# BEP3_RPM_BAR_multi.net
KiCad netlist of a schematic drawn in EAGLE
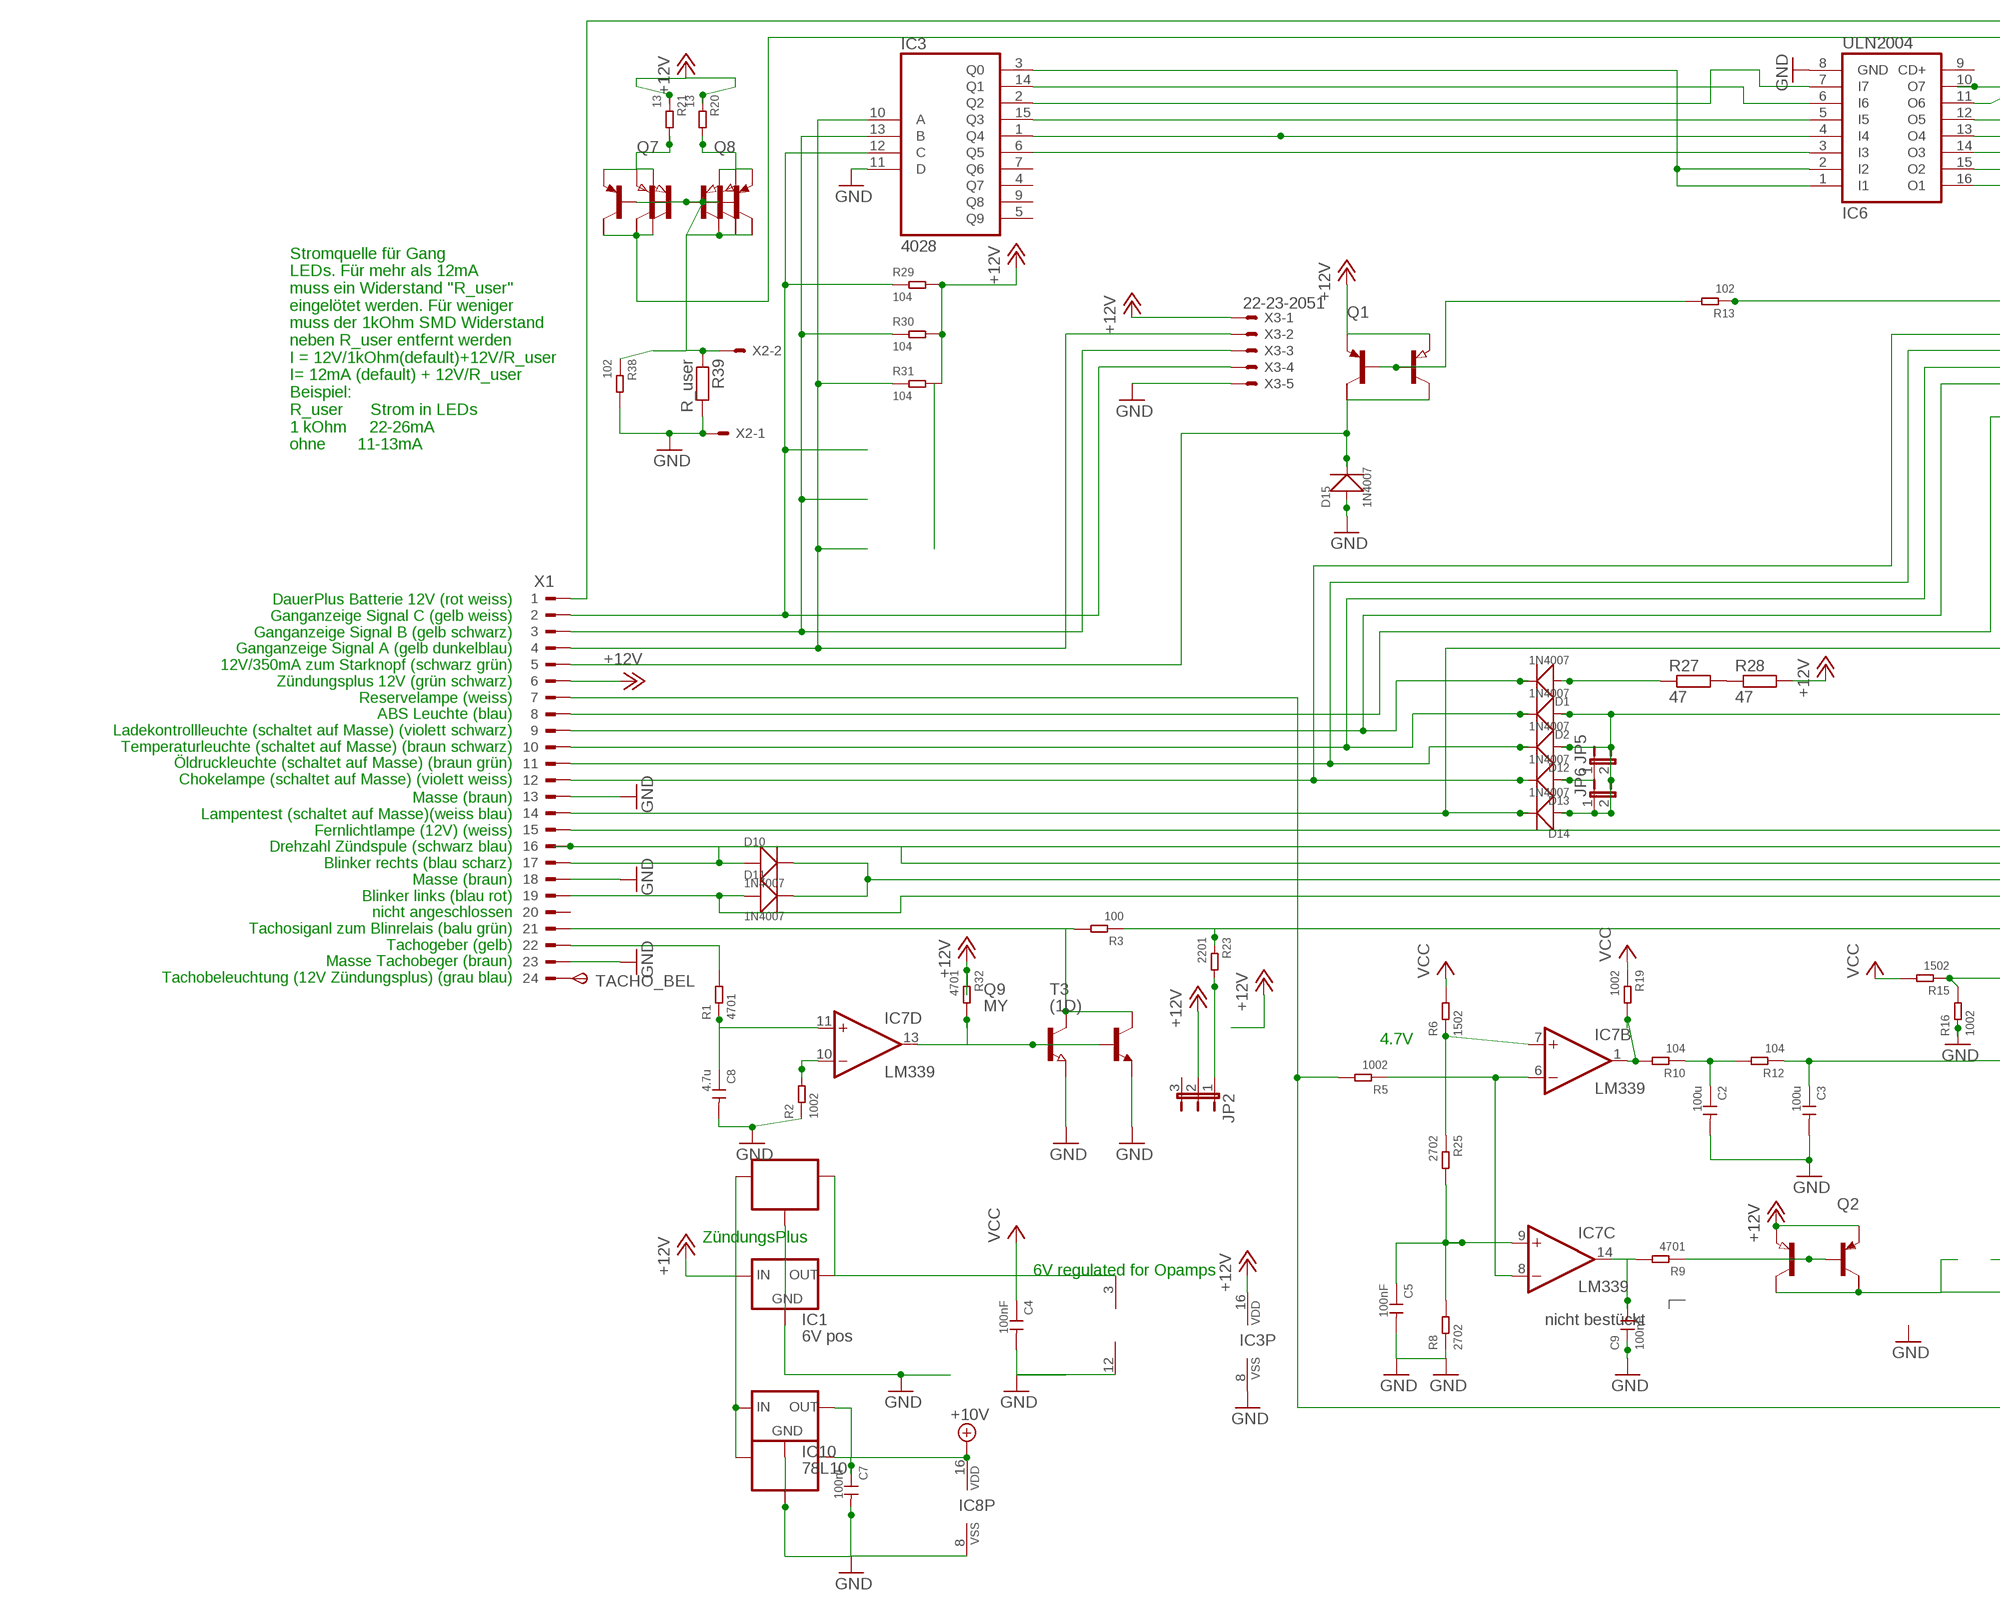
[diagram p0: schematic, sheet 1, part 1 of 2]
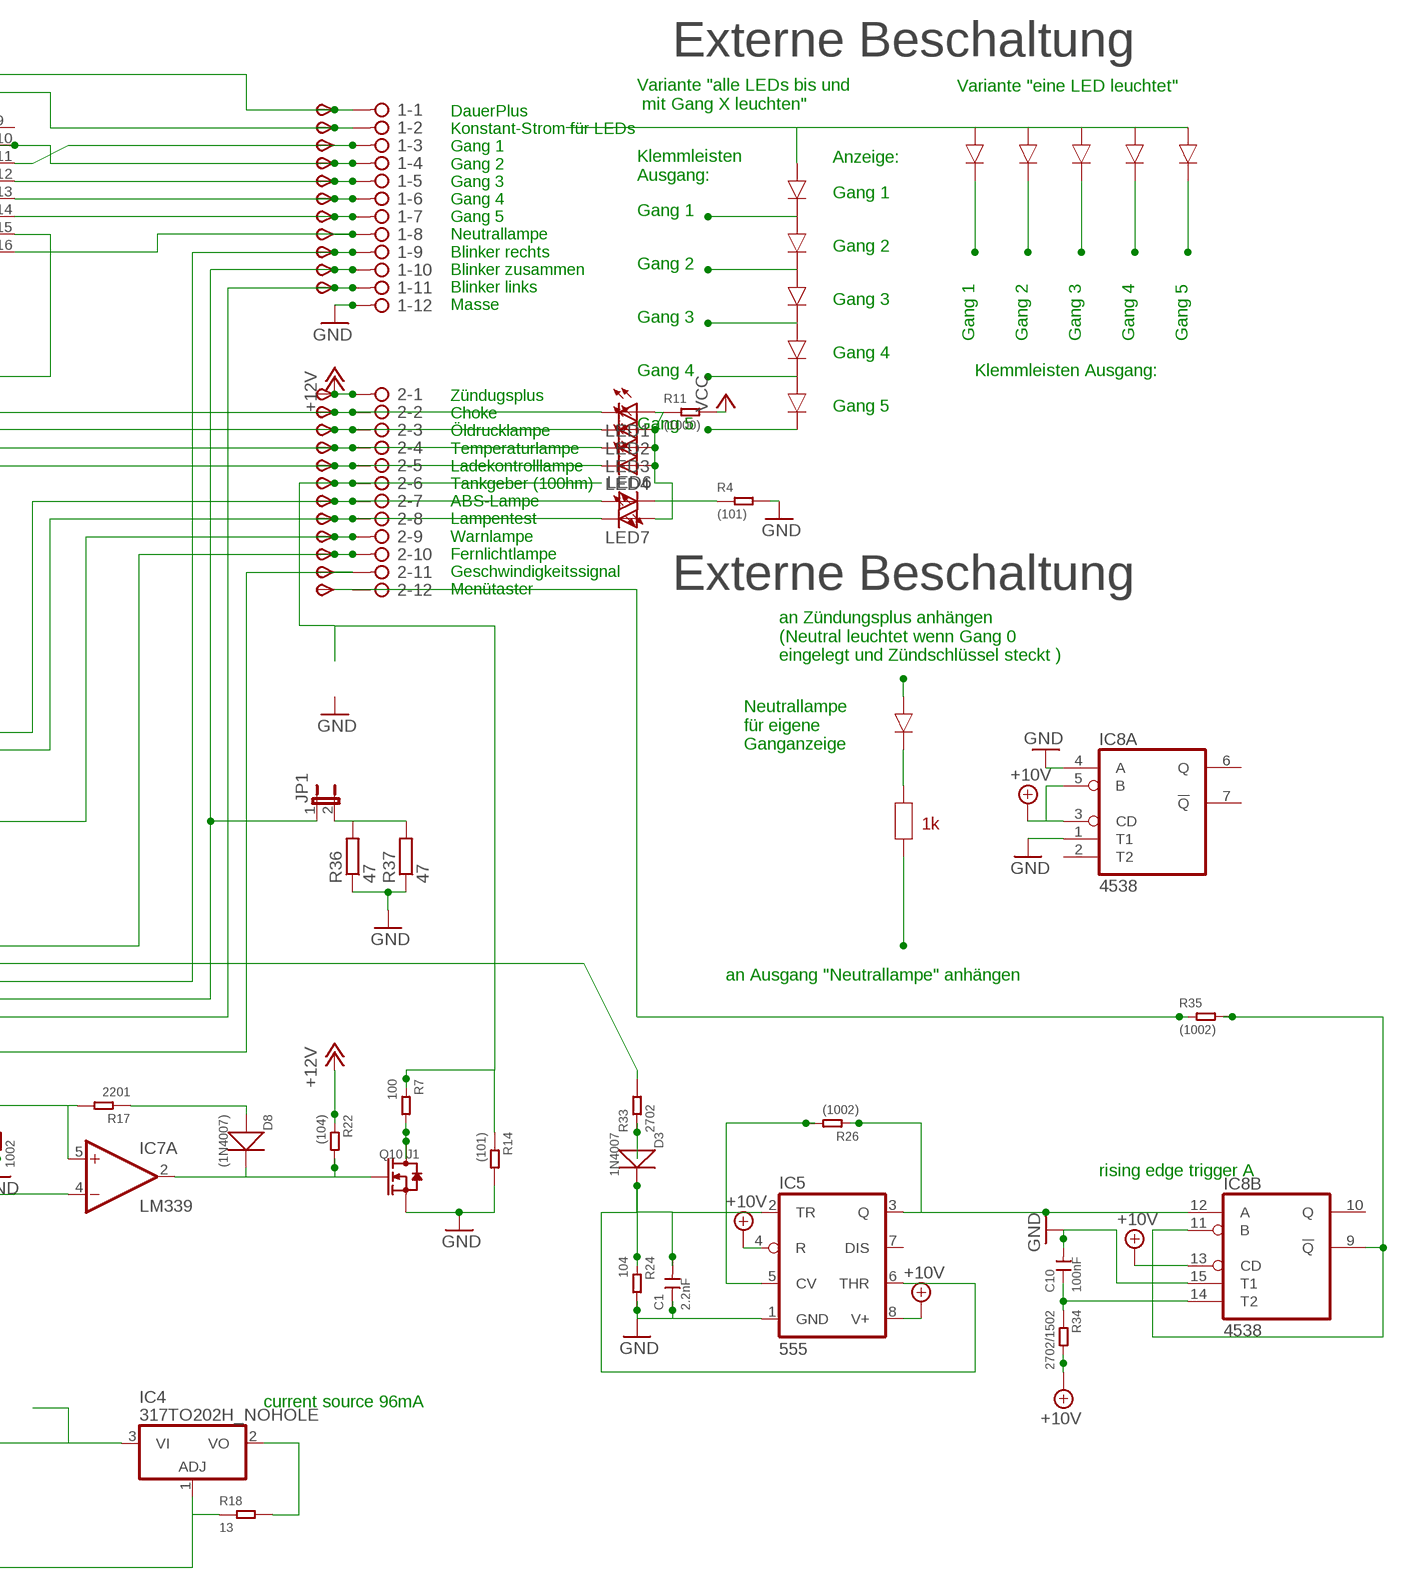
[diagram p1: schematic, sheet 1, part 2 of 2]

(export (version "E")
  (design (tool "Eeschema 10.0.6"))
  (components
    (comp (ref "1")
      (value "2081-1132")
      (footprint "eagle-import:12-PIN")
      (libsource (lib "eagle-import") (part "2081-1132"))
    )
    (comp (ref "2")
      (value "2081-1132")
      (footprint "eagle-import:12-PIN")
      (libsource (lib "eagle-import") (part "2081-1132"))
    )
    (comp (ref "C1")
      (value "2.2nF")
      (footprint "eagle-import:C0805")
      (fields (field (name "MPN") "CC0805KRX7R9BB104"))
      (libsource (lib "eagle-import") (part "CERAMIC-100NF-50V-10%-X7R(0805)"))
    )
    (comp (ref "C2")
      (value "100u")
      (footprint "eagle-import:C1206")
      (fields (field (name "MPN") "GRM31CR60J107ME39L"))
      (libsource (lib "eagle-import") (part "CERAMIC-100UF-6.3V-20%-X5R(1206)"))
    )
    (comp (ref "C3")
      (value "100u")
      (footprint "eagle-import:C1206")
      (fields (field (name "MPN") "GRM31CR60J107ME39L"))
      (libsource (lib "eagle-import") (part "CERAMIC-100UF-6.3V-20%-X5R(1206)"))
    )
    (comp (ref "C4")
      (value "100nF")
      (footprint "eagle-import:C0805")
      (fields (field (name "MPN") "CC0805KRX7R9BB104"))
      (libsource (lib "eagle-import") (part "CERAMIC-100NF-50V-10%-X7R(0805)"))
    )
    (comp (ref "C5")
      (value "100nF")
      (footprint "eagle-import:C0805")
      (fields (field (name "MPN") "CC0805KRX7R9BB104"))
      (libsource (lib "eagle-import") (part "CERAMIC-100NF-50V-10%-X7R(0805)"))
    )
    (comp (ref "C7")
      (value "100nF")
      (footprint "eagle-import:C0805")
      (fields (field (name "MPN") "CC0805KRX7R9BB104"))
      (libsource (lib "eagle-import") (part "CERAMIC-100NF-50V-10%-X7R(0805)"))
    )
    (comp (ref "C8")
      (value "4.7u")
      (footprint "eagle-import:C0805")
      (fields (field (name "MPN") "CC0805KKX5R8BB475"))
      (libsource (lib "eagle-import") (part "CERAMIC-4.7UF-25V-10%-X5R(0805)"))
    )
    (comp (ref "C9")
      (value "100nF")
      (footprint "eagle-import:C0805")
      (fields (field (name "MPN") "CC0805KRX7R9BB104"))
      (libsource (lib "eagle-import") (part "CERAMIC-100NF-50V-10%-X7R(0805)"))
    )
    (comp (ref "C10")
      (value "100nF")
      (footprint "eagle-import:C0805")
      (fields (field (name "MPN") "CC0805KRX7R9BB104"))
      (libsource (lib "eagle-import") (part "CERAMIC-100NF-50V-10%-X7R(0805)"))
    )
    (comp (ref "D1")
      (value "1N4007")
      (footprint "eagle-import:DO-214AC")
      (libsource (lib "eagle-import") (part "DIODE-GEN-PURPOSE-1KV-1A(DO-214AC)"))
    )
    (comp (ref "D2")
      (value "1N4007")
      (footprint "eagle-import:DO-214AC-1206MOUNT")
      (libsource (lib "eagle-import") (part "DIODE-GEN-PURPOSE-1KV-1A(DO-214AC)DO-214AC/1206"))
    )
    (comp (ref "D3")
      (value "1N4007")
      (footprint "eagle-import:DO-214AC")
      (libsource (lib "eagle-import") (part "DIODE-GEN-PURPOSE-1KV-1A(DO-214AC)"))
    )
    (comp (ref "D8")
      (value "(1N4007)")
      (footprint "eagle-import:DO-214AC-1206MOUNT")
      (libsource (lib "eagle-import") (part "DIODE-GEN-PURPOSE-1KV-1A(DO-214AC)DO-214AC/1206"))
    )
    (comp (ref "D10")
      (value "1N4007")
      (footprint "eagle-import:DO-214AC")
      (libsource (lib "eagle-import") (part "DIODE-GEN-PURPOSE-1KV-1A(DO-214AC)"))
    )
    (comp (ref "D11")
      (value "1N4007")
      (footprint "eagle-import:DO-214AC")
      (libsource (lib "eagle-import") (part "DIODE-GEN-PURPOSE-1KV-1A(DO-214AC)"))
    )
    (comp (ref "D12")
      (value "1N4007")
      (footprint "eagle-import:DO-214AC-1206MOUNT")
      (libsource (lib "eagle-import") (part "DIODE-GEN-PURPOSE-1KV-1A(DO-214AC)DO-214AC/1206"))
    )
    (comp (ref "D13")
      (value "1N4007")
      (footprint "eagle-import:DO-214AC-1206MOUNT")
      (libsource (lib "eagle-import") (part "DIODE-GEN-PURPOSE-1KV-1A(DO-214AC)DO-214AC/1206"))
    )
    (comp (ref "D14")
      (value "1N4007")
      (footprint "eagle-import:DO-214AC-1206MOUNT")
      (libsource (lib "eagle-import") (part "DIODE-GEN-PURPOSE-1KV-1A(DO-214AC)DO-214AC/1206"))
    )
    (comp (ref "D15")
      (value "1N4007")
      (footprint "eagle-import:DO-214AC")
      (libsource (lib "eagle-import") (part "DIODE-GEN-PURPOSE-1KV-1A(DO-214AC)"))
    )
    (comp (ref "IC1")
      (value "6V pos")
      (footprint "eagle-import:78LXX")
      (libsource (lib "eagle-import") (part "v-reg_78LXX"))
    )
    (comp (ref "IC2")
      (value "78LXX-SOT89")
      (footprint "eagle-import:SOT89")
      (libsource (lib "eagle-import") (part "78LXX-SOT89"))
    )
    (comp (ref "IC3")
      (value "4028")
      (footprint "eagle-import:SO16")
      (libsource (lib "eagle-import") (part "4028D"))
    )
    (comp (ref "IC4")
      (value "317TO202H_NOHOLE")
      (footprint "eagle-import:TO220H_NOHOLE")
      (libsource (lib "eagle-import") (part "317TO202H_NOHOLE"))
    )
    (comp (ref "IC5")
      (value "555")
      (footprint "eagle-import:SO08")
      (libsource (lib "eagle-import") (part "555DNE"))
    )
    (comp (ref "IC6")
      (value "ULN2004")
      (footprint "eagle-import:SO16")
      (libsource (lib "eagle-import") (part "ULN2004AD"))
    )
    (comp (ref "IC7")
      (value "LM339")
      (footprint "eagle-import:SO14")
      (libsource (lib "eagle-import") (part "LM339D"))
    )
    (comp (ref "IC8")
      (value "4538")
      (footprint "eagle-import:SO16")
      (libsource (lib "eagle-import") (part "4538D"))
    )
    (comp (ref "IC9")
      (value "78LXX-SOT89")
      (footprint "eagle-import:SOT89")
      (libsource (lib "eagle-import") (part "78LXX-SOT89"))
    )
    (comp (ref "IC10")
      (value "78L10")
      (footprint "eagle-import:78LXX")
      (libsource (lib "eagle-import") (part "v-reg_78LXX"))
    )
    (comp (ref "JP1")
      (value "JP1E")
      (footprint "eagle-import:JP1")
      (libsource (lib "eagle-import") (part "JP1E"))
    )
    (comp (ref "JP2")
      (value "JP2E")
      (footprint "eagle-import:JP2")
      (libsource (lib "eagle-import") (part "JP2E"))
    )
    (comp (ref "JP5")
      (value "JP1E")
      (footprint "eagle-import:JP1")
      (libsource (lib "eagle-import") (part "JP1E"))
    )
    (comp (ref "JP6")
      (value "JP1E")
      (footprint "eagle-import:JP1")
      (libsource (lib "eagle-import") (part "JP1E"))
    )
    (comp (ref "LED1")
      (value "LEDLD260")
      (footprint "eagle-import:LD260")
      (libsource (lib "eagle-import") (part "LEDLD260"))
    )
    (comp (ref "LED2")
      (value "LEDLD260")
      (footprint "eagle-import:LD260")
      (libsource (lib "eagle-import") (part "LEDLD260"))
    )
    (comp (ref "LED3")
      (value "LEDLD260")
      (footprint "eagle-import:LD260")
      (libsource (lib "eagle-import") (part "LEDLD260"))
    )
    (comp (ref "LED4")
      (value "LEDLD260")
      (footprint "eagle-import:LD260")
      (libsource (lib "eagle-import") (part "LEDLD260"))
    )
    (comp (ref "LED6")
      (value "LEDLD260")
      (footprint "eagle-import:LD260")
      (libsource (lib "eagle-import") (part "LEDLD260"))
    )
    (comp (ref "LED7")
      (value "LEDLD260")
      (footprint "eagle-import:LD260")
      (libsource (lib "eagle-import") (part "LEDLD260"))
    )
    (comp (ref "Q1")
      (value "PNP-TRANSISTOR_SOT89")
      (footprint "eagle-import:SOT89")
      (libsource (lib "eagle-import") (part "PNP-TRANSISTOR_SOT89"))
    )
    (comp (ref "Q2")
      (value "PNP-TRANSISTOR_SOT89")
      (footprint "eagle-import:SOT89")
      (libsource (lib "eagle-import") (part "PNP-TRANSISTOR_SOT89"))
    )
    (comp (ref "Q3")
      (value "AH-16")
      (footprint "eagle-import:SOT223")
      (libsource (lib "eagle-import") (part "BCP53T1"))
    )
    (comp (ref "Q4")
      (value "(AH-16)")
      (footprint "eagle-import:SOT223")
      (libsource (lib "eagle-import") (part "BCP53T1"))
    )
    (comp (ref "Q5")
      (value "(AH-16)")
      (footprint "eagle-import:SOT223")
      (libsource (lib "eagle-import") (part "BCP53T1"))
    )
    (comp (ref "Q6")
      (value "(AH-16)")
      (footprint "eagle-import:SOT223")
      (libsource (lib "eagle-import") (part "BCP53T1"))
    )
    (comp (ref "Q7")
      (value "PNP-TRANSISTOR_SOT89")
      (footprint "eagle-import:SOT89")
      (libsource (lib "eagle-import") (part "PNP-TRANSISTOR_SOT89"))
    )
    (comp (ref "Q8")
      (value "PNP-TRANSISTOR_SOT89")
      (footprint "eagle-import:SOT89")
      (libsource (lib "eagle-import") (part "PNP-TRANSISTOR_SOT89"))
    )
    (comp (ref "Q9")
      (value "MY")
      (footprint "eagle-import:SOT89")
      (libsource (lib "eagle-import") (part "NPN-TRANSISTOR_SOT89"))
    )
    (comp (ref "Q10")
      (value "J1")
      (footprint "eagle-import:SOT-23")
      (fields (field (name "MPN") "BSS138W-7-F"))
      (libsource (lib "eagle-import") (part "SMD-MOSFET-N-CH-50V-200MA-BSS138W-7-F(SOT-23)"))
    )
    (comp (ref "R1")
      (value "4701")
      (footprint "eagle-import:R0805")
      (fields (field (name "MPN") "RC0805JR-074K7L"))
      (libsource (lib "eagle-import") (part "SMD-RES-4.7K-5%-1/8W(0805)"))
    )
    (comp (ref "R2")
      (value "1002")
      (footprint "eagle-import:R0805")
      (fields (field (name "MPN") "RC0805FR-0710KL"))
      (libsource (lib "eagle-import") (part "SMD-RES-10K-1%-1/8W(0805)"))
    )
    (comp (ref "R3")
      (value "100")
      (footprint "eagle-import:R0805")
      (fields (field (name "MPN") "RC0805JR-07220RL"))
      (libsource (lib "eagle-import") (part "SMD-RES-220R-5%-1/8W(0805)"))
    )
    (comp (ref "R4")
      (value "(101)")
      (footprint "eagle-import:R0805")
      (fields (field (name "MPN") "RC0805JR-07100RL"))
      (libsource (lib "eagle-import") (part "SMD-RES-100R-5%-1/8W(0805)"))
    )
    (comp (ref "R5")
      (value "1002")
      (footprint "eagle-import:R0805")
      (fields (field (name "MPN") "RC0805FR-0710KL"))
      (libsource (lib "eagle-import") (part "SMD-RES-10K-1%-1/8W(0805)"))
    )
    (comp (ref "R6")
      (value "1502")
      (footprint "eagle-import:R0805")
      (fields (field (name "MPN") "RC0805FR-0710KL"))
      (libsource (lib "eagle-import") (part "SMD-RES-10K-1%-1/8W(0805)"))
    )
    (comp (ref "R7")
      (value "100")
      (footprint "eagle-import:R0805")
      (fields (field (name "MPN") "RC0805JR-072K2L"))
      (libsource (lib "eagle-import") (part "SMD-RES-2.2K-5%-1/8W(0805)"))
    )
    (comp (ref "R8")
      (value "2702")
      (footprint "eagle-import:R0805")
      (fields (field (name "MPN") "RC0805JR-074K7L"))
      (libsource (lib "eagle-import") (part "SMD-RES-4.7K-5%-1/8W(0805)"))
    )
    (comp (ref "R9")
      (value "4701")
      (footprint "eagle-import:R0805")
      (fields (field (name "MPN") "RC0805JR-074K7L"))
      (libsource (lib "eagle-import") (part "SMD-RES-4.7K-5%-1/8W(0805)"))
    )
    (comp (ref "R10")
      (value "104")
      (footprint "eagle-import:R0805")
      (fields (field (name "MPN") "RC0805FR-0710KL"))
      (libsource (lib "eagle-import") (part "SMD-RES-10K-1%-1/8W(0805)"))
    )
    (comp (ref "R11")
      (value "(1000)")
      (footprint "eagle-import:R0805")
      (fields (field (name "MPN") "RC0805JR-07100RL"))
      (libsource (lib "eagle-import") (part "SMD-RES-100R-5%-1/8W(0805)"))
    )
    (comp (ref "R12")
      (value "104")
      (footprint "eagle-import:R0805")
      (fields (field (name "MPN") "RC0805FR-0710KL"))
      (libsource (lib "eagle-import") (part "SMD-RES-10K-1%-1/8W(0805)"))
    )
    (comp (ref "R13")
      (value "102")
      (footprint "eagle-import:R0805")
      (fields (field (name "MPN") "RC0805JR-071KL"))
      (libsource (lib "eagle-import") (part "SMD-RES-1K-5%-1/8W(0805)"))
    )
    (comp (ref "R14")
      (value "(101)")
      (footprint "eagle-import:R0805")
      (fields (field (name "MPN") "RC0805JR-072K2L"))
      (libsource (lib "eagle-import") (part "SMD-RES-2.2K-5%-1/8W(0805)"))
    )
    (comp (ref "R15")
      (value "1502")
      (footprint "eagle-import:R0805")
      (fields (field (name "MPN") "RC0805FR-0710KL"))
      (libsource (lib "eagle-import") (part "SMD-RES-10K-1%-1/8W(0805)"))
    )
    (comp (ref "R16")
      (value "1002")
      (footprint "eagle-import:R0805")
      (fields (field (name "MPN") "RC0805FR-0710KL"))
      (libsource (lib "eagle-import") (part "SMD-RES-10K-1%-1/8W(0805)"))
    )
    (comp (ref "R17")
      (value "2201")
      (footprint "eagle-import:R0805")
      (fields (field (name "MPN") "RC0805JR-072K2L"))
      (libsource (lib "eagle-import") (part "SMD-RES-2.2K-5%-1/8W(0805)"))
    )
    (comp (ref "R18")
      (value "13")
      (footprint "eagle-import:R1206")
      (fields (field (name "MPN") "RC1206JR-0713RL"))
      (libsource (lib "eagle-import") (part "SMD-RES-13R-5%-1/4W(1206)"))
    )
    (comp (ref "R19")
      (value "1002")
      (footprint "eagle-import:R0805")
      (fields (field (name "MPN") "RC0805FR-0710KL"))
      (libsource (lib "eagle-import") (part "SMD-RES-10K-1%-1/8W(0805)"))
    )
    (comp (ref "R20")
      (value "13")
      (footprint "eagle-import:R1206")
      (fields (field (name "MPN") "RC1206JR-0713RL"))
      (libsource (lib "eagle-import") (part "SMD-RES-13R-5%-1/4W(1206)"))
    )
    (comp (ref "R21")
      (value "13")
      (footprint "eagle-import:R1206")
      (fields (field (name "MPN") "RC1206JR-0713RL"))
      (libsource (lib "eagle-import") (part "SMD-RES-13R-5%-1/4W(1206)"))
    )
    (comp (ref "R22")
      (value "(104)")
      (footprint "eagle-import:R0805")
      (fields (field (name "MPN") "RC0805FR-0710KL"))
      (libsource (lib "eagle-import") (part "SMD-RES-10K-1%-1/8W(0805)"))
    )
    (comp (ref "R23")
      (value "2201")
      (footprint "eagle-import:R0805")
      (fields (field (name "MPN") "RC0805JR-072K2L"))
      (libsource (lib "eagle-import") (part "SMD-RES-2.2K-5%-1/8W(0805)"))
    )
    (comp (ref "R24")
      (value "104")
      (footprint "eagle-import:R0805")
      (fields (field (name "MPN") "RC0805FR-0710KL"))
      (libsource (lib "eagle-import") (part "SMD-RES-10K-1%-1/8W(0805)"))
    )
    (comp (ref "R25")
      (value "2702")
      (footprint "eagle-import:R0805")
      (fields (field (name "MPN") "RC0805JR-074K7L"))
      (libsource (lib "eagle-import") (part "SMD-RES-4.7K-5%-1/8W(0805)"))
    )
    (comp (ref "R26")
      (value "(1002)")
      (footprint "eagle-import:R0805")
      (fields (field (name "MPN") "RC0805FR-0710KL"))
      (libsource (lib "eagle-import") (part "SMD-RES-10K-1%-1/8W(0805)"))
    )
    (comp (ref "R27")
      (value "47")
      (footprint "eagle-import:V235_17_1MM")
      (libsource (lib "eagle-import") (part "R-EU_V235/17_1MM"))
    )
    (comp (ref "R28")
      (value "47")
      (footprint "eagle-import:V235_17_1MM")
      (libsource (lib "eagle-import") (part "R-EU_V235/17_1MM"))
    )
    (comp (ref "R29")
      (value "104")
      (footprint "eagle-import:R0805")
      (fields (field (name "MPN") "RC0805FR-0710KL"))
      (libsource (lib "eagle-import") (part "SMD-RES-10K-1%-1/8W(0805)"))
    )
    (comp (ref "R30")
      (value "104")
      (footprint "eagle-import:R0805")
      (fields (field (name "MPN") "RC0805FR-0710KL"))
      (libsource (lib "eagle-import") (part "SMD-RES-10K-1%-1/8W(0805)"))
    )
    (comp (ref "R31")
      (value "104")
      (footprint "eagle-import:R0805")
      (fields (field (name "MPN") "RC0805FR-0710KL"))
      (libsource (lib "eagle-import") (part "SMD-RES-10K-1%-1/8W(0805)"))
    )
    (comp (ref "R32")
      (value "4701")
      (footprint "eagle-import:R0805")
      (fields (field (name "MPN") "RC0805JR-074K7L"))
      (libsource (lib "eagle-import") (part "SMD-RES-4.7K-5%-1/8W(0805)"))
    )
    (comp (ref "R33")
      (value "2702")
      (footprint "eagle-import:R0805")
      (fields (field (name "MPN") "RC0805FR-0710KL"))
      (libsource (lib "eagle-import") (part "SMD-RES-10K-1%-1/8W(0805)"))
    )
    (comp (ref "R34")
      (value "2702/1502")
      (footprint "eagle-import:R0805")
      (fields (field (name "MPN") "RC0805JR-074K7L"))
      (libsource (lib "eagle-import") (part "SMD-RES-4.7K-5%-1/8W(0805)"))
    )
    (comp (ref "R35")
      (value "(1002)")
      (footprint "eagle-import:R0805")
      (fields (field (name "MPN") "RC0805JR-074K7L"))
      (libsource (lib "eagle-import") (part "SMD-RES-4.7K-5%-1/8W(0805)"))
    )
    (comp (ref "R36")
      (value "47")
      (footprint "eagle-import:V235_17_1MM")
      (libsource (lib "eagle-import") (part "R-EU_V235/17_1MM"))
    )
    (comp (ref "R37")
      (value "47")
      (footprint "eagle-import:V235_17_1MM")
      (libsource (lib "eagle-import") (part "R-EU_V235/17_1MM"))
    )
    (comp (ref "R38")
      (value "102")
      (footprint "eagle-import:R0805")
      (fields (field (name "MPN") "RC0805JR-071KL"))
      (libsource (lib "eagle-import") (part "SMD-RES-1K-5%-1/8W(0805)"))
    )
    (comp (ref "R39")
      (value "R_user")
      (footprint "eagle-import:R0805")
      (libsource (lib "eagle-import") (part "R-EU_R0805"))
    )
    (comp (ref "T1")
      (value "PNP2SM8")
      (footprint "eagle-import:SM8")
      (libsource (lib "eagle-import") (part "PNP2SM8"))
    )
    (comp (ref "T3")
      (value "(1D)")
      (footprint "eagle-import:SOT23-BEC")
      (libsource (lib "eagle-import") (part "-NPN-SOT23-BECMMBTA42LT1"))
    )
    (comp (ref "TACHO_BEL")
      (value "TPSP1_1MM")
      (footprint "eagle-import:P1_1.0MM")
      (libsource (lib "eagle-import") (part "TPSP1_1MM"))
    )
    (comp (ref "TP1")
      (value "TPSB1.8")
      (footprint "eagle-import:B1.8")
      (libsource (lib "eagle-import") (part "TPSB1.8"))
    )
    (comp (ref "TP2")
      (value "TPSB1.8")
      (footprint "eagle-import:B1.8")
      (libsource (lib "eagle-import") (part "TPSB1.8"))
    )
    (comp (ref "TP3")
      (value "TPSB1.8")
      (footprint "eagle-import:B1.8")
      (libsource (lib "eagle-import") (part "TPSB1.8"))
    )
    (comp (ref "TP4")
      (value "TPSB1.8")
      (footprint "eagle-import:B1.8")
      (libsource (lib "eagle-import") (part "TPSB1.8"))
    )
    (comp (ref "TP5")
      (value "TPSB1.8")
      (footprint "eagle-import:B1.8")
      (libsource (lib "eagle-import") (part "TPSB1.8"))
    )
    (comp (ref "TP6")
      (value "TPSB1.8")
      (footprint "eagle-import:B1.8")
      (libsource (lib "eagle-import") (part "TPSB1.8"))
    )
    (comp (ref "TP7")
      (value "TPSB1.8")
      (footprint "eagle-import:B1.8")
      (libsource (lib "eagle-import") (part "TPSB1.8"))
    )
    (comp (ref "TP8")
      (value "TPSB1.8")
      (footprint "eagle-import:B1.8")
      (libsource (lib "eagle-import") (part "TPSB1.8"))
    )
    (comp (ref "TP9")
      (value "TPSB1.8")
      (footprint "eagle-import:B1.8")
      (libsource (lib "eagle-import") (part "TPSB1.8"))
    )
    (comp (ref "TP10")
      (value "TPSB1.8")
      (footprint "eagle-import:B1.8")
      (libsource (lib "eagle-import") (part "TPSB1.8"))
    )
    (comp (ref "TP11")
      (value "TPSB1.8")
      (footprint "eagle-import:B1.8")
      (libsource (lib "eagle-import") (part "TPSB1.8"))
    )
    (comp (ref "TP12")
      (value "TPSB1.8")
      (footprint "eagle-import:B1.8")
      (libsource (lib "eagle-import") (part "TPSB1.8"))
    )
    (comp (ref "TP13")
      (value "TPSB1,27")
      (footprint "eagle-import:B1,27")
      (libsource (lib "eagle-import") (part "TPSB1,27"))
    )
    (comp (ref "TP16")
      (value "TPSB1.8")
      (footprint "eagle-import:B1.8")
      (libsource (lib "eagle-import") (part "TPSB1.8"))
    )
    (comp (ref "TP17")
      (value "TPSB1.8")
      (footprint "eagle-import:B1.8")
      (libsource (lib "eagle-import") (part "TPSB1.8"))
    )
    (comp (ref "TP18")
      (value "TPSB1.8")
      (footprint "eagle-import:B1.8")
      (libsource (lib "eagle-import") (part "TPSB1.8"))
    )
    (comp (ref "TP19")
      (value "TPSB1.8")
      (footprint "eagle-import:B1.8")
      (libsource (lib "eagle-import") (part "TPSB1.8"))
    )
    (comp (ref "TP21")
      (value "TPSB1.8")
      (footprint "eagle-import:B1.8")
      (libsource (lib "eagle-import") (part "TPSB1.8"))
    )
    (comp (ref "TP22")
      (value "TPSB1.8")
      (footprint "eagle-import:B1.8")
      (libsource (lib "eagle-import") (part "TPSB1.8"))
    )
    (comp (ref "TP23")
      (value "TPSB1.8")
      (footprint "eagle-import:B1.8")
      (libsource (lib "eagle-import") (part "TPSB1.8"))
    )
    (comp (ref "TP24")
      (value "TPSB1,27")
      (footprint "eagle-import:B1,27")
      (libsource (lib "eagle-import") (part "TPSB1,27"))
    )
    (comp (ref "TP25")
      (value "TPSB1.8")
      (footprint "eagle-import:B1.8")
      (libsource (lib "eagle-import") (part "TPSB1.8"))
    )
    (comp (ref "TP26")
      (value "TPSB1.8")
      (footprint "eagle-import:B1.8")
      (libsource (lib "eagle-import") (part "TPSB1.8"))
    )
    (comp (ref "X1")
      (value "CON_BMWV2")
      (footprint "eagle-import:24-PIN_V2")
      (libsource (lib "eagle-import") (part "CON_BMWV2"))
    )
    (comp (ref "X2")
      (value "22-23-2021")
      (footprint "eagle-import:22-23-2021")
      (fields (field (name "MF") "MOLEX"))
      (libsource (lib "eagle-import") (part "22-23-2021"))
    )
    (comp (ref "X3")
      (value "22-23-2051")
      (footprint "eagle-import:22-23-2051")
      (fields (field (name "MF") "MOLEX"))
      (libsource (lib "eagle-import") (part "22-23-2051"))
    )
  )
  (nets
    (net (code "1") (name "+10V") (class "Default")
      (node (ref "C7") (pin "1") (pinfunction "1_1") (pintype "passive"))
      (node (ref "IC10") (pin "OUT") (pinfunction "OUT_OUT") (pintype "passive"))
      (node (ref "IC5") (pin "4") (pinfunction "R_4") (pintype "input"))
      (node (ref "IC5") (pin "8") (pinfunction "V+_8") (pintype "power_in"))
      (node (ref "IC8") (pin "13") (pinfunction "CD_13") (pintype "input"))
      (node (ref "IC8") (pin "16") (pinfunction "VDD_16") (pintype "power_in"))
      (node (ref "IC8") (pin "3") (pinfunction "CD_3") (pintype "input"))
      (node (ref "IC8") (pin "5") (pinfunction "B_5") (pintype "input"))
      (node (ref "IC9") (pin "1") (pinfunction "OUT_1") (pintype "passive"))
      (node (ref "R34") (pin "2") (pinfunction "2_2") (pintype "passive"))
    )
    (net (code "2") (name "+12V") (class "Default")
      (node (ref "2") (pin "1") (pinfunction "KL_1") (pintype "passive"))
      (node (ref "IC1") (pin "IN") (pinfunction "IN_IN") (pintype "input"))
      (node (ref "IC10") (pin "IN") (pinfunction "IN_IN") (pintype "input"))
      (node (ref "IC2") (pin "3") (pinfunction "IN_3") (pintype "input"))
      (node (ref "IC3") (pin "16") (pinfunction "VDD_16") (pintype "power_in"))
      (node (ref "IC9") (pin "3") (pinfunction "IN_3") (pintype "input"))
      (node (ref "JP2") (pin "2") (pinfunction "2_2") (pintype "passive"))
      (node (ref "Q1") (pin "3") (pinfunction "E_3") (pintype "passive"))
      (node (ref "Q2") (pin "3") (pinfunction "E_3") (pintype "passive"))
      (node (ref "Q3") (pin "3") (pinfunction "E_3") (pintype "passive"))
      (node (ref "Q4") (pin "3") (pinfunction "E_3") (pintype "passive"))
      (node (ref "R20") (pin "1") (pinfunction "1_1") (pintype "passive"))
      (node (ref "R21") (pin "1") (pinfunction "1_1") (pintype "passive"))
      (node (ref "R22") (pin "1") (pinfunction "1_1") (pintype "passive"))
      (node (ref "R28") (pin "2") (pinfunction "2_2") (pintype "passive"))
      (node (ref "R29") (pin "2") (pinfunction "2_2") (pintype "passive"))
      (node (ref "R30") (pin "2") (pinfunction "2_2") (pintype "passive"))
      (node (ref "R31") (pin "2") (pinfunction "2_2") (pintype "passive"))
      (node (ref "R32") (pin "1") (pinfunction "1_1") (pintype "passive"))
      (node (ref "TP12") (pin "TP") (pinfunction "PP_TP") (pintype "input"))
      (node (ref "X1") (pin "6") (pinfunction "6_6") (pintype "passive"))
      (node (ref "X3") (pin "1") (pinfunction "S_1") (pintype "passive"))
    )
    (net (code "3") (name "GND") (class "Default")
      (node (ref "1") (pin "12") (pinfunction "KL_12") (pintype "passive"))
      (node (ref "C1") (pin "1") (pinfunction "1_1") (pintype "passive"))
      (node (ref "C10") (pin "2") (pinfunction "2_2") (pintype "passive"))
      (node (ref "C2") (pin "2") (pinfunction "2_2") (pintype "passive"))
      (node (ref "C3") (pin "2") (pinfunction "2_2") (pintype "passive"))
      (node (ref "C4") (pin "2") (pinfunction "2_2") (pintype "passive"))
      (node (ref "C5") (pin "2") (pinfunction "2_2") (pintype "passive"))
      (node (ref "C7") (pin "2") (pinfunction "2_2") (pintype "passive"))
      (node (ref "C8") (pin "2") (pinfunction "2_2") (pintype "passive"))
      (node (ref "C9") (pin "1") (pinfunction "1_1") (pintype "passive"))
      (node (ref "D15") (pin "1") (pinfunction "+_1") (pintype "passive"))
      (node (ref "IC1") (pin "GND") (pinfunction "GND_GND") (pintype "input"))
      (node (ref "IC10") (pin "GND") (pinfunction "GND_GND") (pintype "input"))
      (node (ref "IC2") (pin "2") (pinfunction "GND_2") (pintype "input"))
      (node (ref "IC2") (pin "4") (pinfunction "GND_4") (pintype "input"))
      (node (ref "IC3") (pin "11") (pinfunction "D_11") (pintype "input"))
      (node (ref "IC3") (pin "8") (pinfunction "VSS_8") (pintype "power_in"))
      (node (ref "IC5") (pin "1") (pinfunction "GND_1") (pintype "power_in"))
      (node (ref "IC6") (pin "8") (pinfunction "GND_8") (pintype "power_in"))
      (node (ref "IC7") (pin "12") (pinfunction "GND_12") (pintype "power_in"))
      (node (ref "IC8") (pin "1") (pinfunction "T1_1") (pintype "input"))
      (node (ref "IC8") (pin "15") (pinfunction "T1_15") (pintype "input"))
      (node (ref "IC8") (pin "4") (pinfunction "A_4") (pintype "input"))
      (node (ref "IC8") (pin "8") (pinfunction "VSS_8") (pintype "power_in"))
      (node (ref "IC9") (pin "2") (pinfunction "GND_2") (pintype "input"))
      (node (ref "IC9") (pin "4") (pinfunction "GND_4") (pintype "input"))
      (node (ref "Q10") (pin "2") (pinfunction "S_2") (pintype "passive"))
      (node (ref "Q9") (pin "3") (pinfunction "E_3") (pintype "passive"))
      (node (ref "R14") (pin "2") (pinfunction "2_2") (pintype "passive"))
      (node (ref "R16") (pin "1") (pinfunction "1_1") (pintype "passive"))
      (node (ref "R2") (pin "1") (pinfunction "1_1") (pintype "passive"))
      (node (ref "R24") (pin "2") (pinfunction "2_2") (pintype "passive"))
      (node (ref "R36") (pin "1") (pinfunction "1_1") (pintype "passive"))
      (node (ref "R37") (pin "1") (pinfunction "1_1") (pintype "passive"))
      (node (ref "R38") (pin "2") (pinfunction "2_2") (pintype "passive"))
      (node (ref "R39") (pin "2") (pinfunction "2_2") (pintype "passive"))
      (node (ref "R4") (pin "2") (pinfunction "2_2") (pintype "passive"))
      (node (ref "R8") (pin "1") (pinfunction "1_1") (pintype "passive"))
      (node (ref "T3") (pin "E") (pinfunction "E_E") (pintype "passive"))
      (node (ref "X1") (pin "13") (pinfunction "13_13") (pintype "passive"))
      (node (ref "X1") (pin "18") (pinfunction "18_18") (pintype "passive"))
      (node (ref "X1") (pin "23") (pinfunction "23_23") (pintype "passive"))
      (node (ref "X2") (pin "1") (pinfunction "S_1") (pintype "passive"))
      (node (ref "X3") (pin "5") (pinfunction "S_5") (pintype "passive"))
    )
    (net (code "4") (name "Net-(1A-KL)") (class "Default")
      (node (ref "1") (pin "1") (pinfunction "KL_1") (pintype "passive"))
      (node (ref "TP1") (pin "TP") (pinfunction "PP_TP") (pintype "input"))
      (node (ref "X1") (pin "1") (pinfunction "1_1") (pintype "passive"))
    )
    (net (code "5") (name "Net-(1B-KL)") (class "Default")
      (node (ref "1") (pin "10") (pinfunction "KL_10") (pintype "passive"))
      (node (ref "D10") (pin "2") (pinfunction "-_2") (pintype "passive"))
      (node (ref "D11") (pin "2") (pinfunction "-_2") (pintype "passive"))
      (node (ref "JP1") (pin "1") (pinfunction "1_1") (pintype "passive"))
      (node (ref "TP10") (pin "TP") (pinfunction "PP_TP") (pintype "input"))
    )
    (net (code "6") (name "Net-(1C-KL)") (class "Default")
      (node (ref "1") (pin "11") (pinfunction "KL_11") (pintype "passive"))
      (node (ref "D11") (pin "1") (pinfunction "+_1") (pintype "passive"))
      (node (ref "TP11") (pin "TP") (pinfunction "PP_TP") (pintype "input"))
      (node (ref "X1") (pin "19") (pinfunction "19_19") (pintype "passive"))
    )
    (net (code "7") (name "Net-(1E-KL)") (class "Default")
      (node (ref "1") (pin "2") (pinfunction "KL_2") (pintype "passive"))
      (node (ref "Q5") (pin "2") (pinfunction "C_2") (pintype "passive"))
      (node (ref "Q8") (pin "2") (pinfunction "C_2") (pintype "passive"))
      (node (ref "T1") (pin "8") (pinfunction "C1_8") (pintype "passive"))
      (node (ref "TP2") (pin "TP") (pinfunction "PP_TP") (pintype "input"))
    )
    (net (code "8") (name "Net-(1F-KL)") (class "Default")
      (node (ref "1") (pin "3") (pinfunction "KL_3") (pintype "passive"))
      (node (ref "IC6") (pin "11") (pinfunction "O6_11") (pintype "open_collector"))
      (node (ref "TP3") (pin "TP") (pinfunction "PP_TP") (pintype "input"))
    )
    (net (code "9") (name "Net-(1G-KL)") (class "Default")
      (node (ref "1") (pin "4") (pinfunction "KL_4") (pintype "passive"))
      (node (ref "IC6") (pin "10") (pinfunction "O7_10") (pintype "open_collector"))
      (node (ref "TP4") (pin "TP") (pinfunction "PP_TP") (pintype "input"))
    )
    (net (code "10") (name "Net-(1H-KL)") (class "Default")
      (node (ref "1") (pin "5") (pinfunction "KL_5") (pintype "passive"))
      (node (ref "IC6") (pin "12") (pinfunction "O5_12") (pintype "open_collector"))
      (node (ref "TP5") (pin "TP") (pinfunction "PP_TP") (pintype "input"))
    )
    (net (code "11") (name "Net-(1I-KL)") (class "Default")
      (node (ref "1") (pin "6") (pinfunction "KL_6") (pintype "passive"))
      (node (ref "IC6") (pin "13") (pinfunction "O4_13") (pintype "open_collector"))
      (node (ref "TP6") (pin "TP") (pinfunction "PP_TP") (pintype "input"))
    )
    (net (code "12") (name "Net-(1J-KL)") (class "Default")
      (node (ref "1") (pin "7") (pinfunction "KL_7") (pintype "passive"))
      (node (ref "IC6") (pin "14") (pinfunction "O3_14") (pintype "open_collector"))
      (node (ref "TP7") (pin "TP") (pinfunction "PP_TP") (pintype "input"))
    )
    (net (code "13") (name "Net-(1K-KL)") (class "Default")
      (node (ref "1") (pin "8") (pinfunction "KL_8") (pintype "passive"))
      (node (ref "IC6") (pin "16") (pinfunction "O1_16") (pintype "open_collector"))
      (node (ref "TP8") (pin "TP") (pinfunction "PP_TP") (pintype "input"))
    )
    (net (code "14") (name "Net-(1L-KL)") (class "Default")
      (node (ref "1") (pin "9") (pinfunction "KL_9") (pintype "passive"))
      (node (ref "D10") (pin "1") (pinfunction "+_1") (pintype "passive"))
      (node (ref "TP9") (pin "TP") (pinfunction "PP_TP") (pintype "input"))
      (node (ref "X1") (pin "17") (pinfunction "17_17") (pintype "passive"))
    )
    (net (code "15") (name "Net-(2B-KL)") (class "Default")
      (node (ref "2") (pin "10") (pinfunction "KL_10") (pintype "passive"))
      (node (ref "TP25") (pin "TP") (pinfunction "PP_TP") (pintype "input"))
      (node (ref "X1") (pin "15") (pinfunction "15_15") (pintype "passive"))
    )
    (net (code "16") (name "Net-(2C-KL)") (class "Default")
      (node (ref "2") (pin "11") (pinfunction "KL_11") (pintype "passive"))
      (node (ref "R23") (pin "1") (pinfunction "1_1") (pintype "passive"))
      (node (ref "R3") (pin "1") (pinfunction "1_1") (pintype "passive"))
      (node (ref "TP26") (pin "TP") (pinfunction "PP_TP") (pintype "input"))
    )
    (net (code "17") (name "Net-(2D-KL)") (class "Default")
      (node (ref "2") (pin "12") (pinfunction "KL_12") (pintype "passive"))
      (node (ref "R35") (pin "1") (pinfunction "1_1") (pintype "passive"))
      (node (ref "TP13") (pin "TP") (pinfunction "PP_TP") (pintype "input"))
    )
    (net (code "18") (name "Net-(2E-KL)") (class "Default")
      (node (ref "2") (pin "2") (pinfunction "KL_2") (pintype "passive"))
      (node (ref "D13") (pin "2") (pinfunction "-_2") (pintype "passive"))
      (node (ref "LED1") (pin "K") (pinfunction "C_K") (pintype "passive"))
      (node (ref "TP16") (pin "TP") (pinfunction "PP_TP") (pintype "input"))
      (node (ref "X1") (pin "12") (pinfunction "12_12") (pintype "passive"))
    )
    (net (code "19") (name "Net-(2F-KL)") (class "Default")
      (node (ref "2") (pin "3") (pinfunction "KL_3") (pintype "passive"))
      (node (ref "D12") (pin "2") (pinfunction "-_2") (pintype "passive"))
      (node (ref "LED2") (pin "K") (pinfunction "C_K") (pintype "passive"))
      (node (ref "TP17") (pin "TP") (pinfunction "PP_TP") (pintype "input"))
      (node (ref "X1") (pin "11") (pinfunction "11_11") (pintype "passive"))
    )
    (net (code "20") (name "Net-(2G-KL)") (class "Default")
      (node (ref "2") (pin "4") (pinfunction "KL_4") (pintype "passive"))
      (node (ref "D2") (pin "2") (pinfunction "-_2") (pintype "passive"))
      (node (ref "LED3") (pin "K") (pinfunction "C_K") (pintype "passive"))
      (node (ref "TP18") (pin "TP") (pinfunction "PP_TP") (pintype "input"))
      (node (ref "X1") (pin "10") (pinfunction "10_10") (pintype "passive"))
    )
    (net (code "21") (name "Net-(2H-KL)") (class "Default")
      (node (ref "2") (pin "5") (pinfunction "KL_5") (pintype "passive"))
      (node (ref "D1") (pin "2") (pinfunction "-_2") (pintype "passive"))
      (node (ref "LED4") (pin "K") (pinfunction "C_K") (pintype "passive"))
      (node (ref "TP19") (pin "TP") (pinfunction "PP_TP") (pintype "input"))
      (node (ref "X1") (pin "9") (pinfunction "9_9") (pintype "passive"))
    )
    (net (code "22") (name "Net-(2I-KL)") (class "Default")
      (node (ref "2") (pin "6") (pinfunction "KL_6") (pintype "passive"))
      (node (ref "R14") (pin "1") (pinfunction "1_1") (pintype "passive"))
      (node (ref "R7") (pin "1") (pinfunction "1_1") (pintype "passive"))
      (node (ref "TP21") (pin "TP") (pinfunction "PP_TP") (pintype "input"))
    )
    (net (code "23") (name "Net-(2J-KL)") (class "Default")
      (node (ref "2") (pin "7") (pinfunction "KL_7") (pintype "passive"))
      (node (ref "LED6") (pin "A") (pinfunction "A_A") (pintype "passive"))
      (node (ref "TP22") (pin "TP") (pinfunction "PP_TP") (pintype "input"))
      (node (ref "X1") (pin "8") (pinfunction "8_8") (pintype "passive"))
    )
    (net (code "24") (name "Net-(2K-KL)") (class "Default")
      (node (ref "2") (pin "8") (pinfunction "KL_8") (pintype "passive"))
      (node (ref "D14") (pin "2") (pinfunction "-_2") (pintype "passive"))
      (node (ref "LED7") (pin "K") (pinfunction "C_K") (pintype "passive"))
      (node (ref "TP23") (pin "TP") (pinfunction "PP_TP") (pintype "input"))
      (node (ref "X1") (pin "14") (pinfunction "14_14") (pintype "passive"))
    )
    (net (code "25") (name "Net-(2L-KL)") (class "Default")
      (node (ref "2") (pin "9") (pinfunction "KL_9") (pintype "passive"))
      (node (ref "D12") (pin "1") (pinfunction "+_1") (pintype "passive"))
      (node (ref "D14") (pin "1") (pinfunction "+_1") (pintype "passive"))
      (node (ref "D2") (pin "1") (pinfunction "+_1") (pintype "passive"))
      (node (ref "JP5") (pin "2") (pinfunction "2_2") (pintype "passive"))
      (node (ref "JP6") (pin "1") (pinfunction "1_1") (pintype "passive"))
      (node (ref "JP6") (pin "2") (pinfunction "2_2") (pintype "passive"))
      (node (ref "TP24") (pin "TP") (pinfunction "PP_TP") (pintype "input"))
    )
    (net (code "26") (name "Net-(C2-Pad1)") (class "Default")
      (node (ref "C2") (pin "1") (pinfunction "1_1") (pintype "passive"))
      (node (ref "R10") (pin "1") (pinfunction "1_1") (pintype "passive"))
      (node (ref "R12") (pin "2") (pinfunction "2_2") (pintype "passive"))
    )
    (net (code "27") (name "Net-(D1-+)") (class "Default")
      (node (ref "D1") (pin "1") (pinfunction "+_1") (pintype "passive"))
      (node (ref "R27") (pin "1") (pinfunction "1_1") (pintype "passive"))
    )
    (net (code "28") (name "Net-(D3-+)") (class "Default")
      (node (ref "D3") (pin "1") (pinfunction "+_1") (pintype "passive"))
      (node (ref "R33") (pin "1") (pinfunction "1_1") (pintype "passive"))
    )
    (net (code "29") (name "Net-(D3--)") (class "Default")
      (node (ref "C1") (pin "2") (pinfunction "2_2") (pintype "passive"))
      (node (ref "D3") (pin "2") (pinfunction "-_2") (pintype "passive"))
      (node (ref "IC5") (pin "2") (pinfunction "TR_2") (pintype "input"))
      (node (ref "IC5") (pin "6") (pinfunction "THR_6") (pintype "input"))
      (node (ref "R24") (pin "1") (pinfunction "1_1") (pintype "passive"))
    )
    (net (code "30") (name "Net-(D8-+)") (class "Default")
      (node (ref "D8") (pin "1") (pinfunction "+_1") (pintype "passive"))
      (node (ref "R17") (pin "1") (pinfunction "1_1") (pintype "passive"))
    )
    (net (code "31") (name "Net-(D8--)") (class "Default")
      (node (ref "D8") (pin "2") (pinfunction "-_2") (pintype "passive"))
      (node (ref "IC7") (pin "2") (pinfunction "OUT_2") (pintype "open_collector"))
      (node (ref "Q10") (pin "1") (pinfunction "G_1") (pintype "passive"))
      (node (ref "R22") (pin "2") (pinfunction "2_2") (pintype "passive"))
    )
    (net (code "32") (name "Net-(D13-+)") (class "Default")
      (node (ref "D13") (pin "1") (pinfunction "+_1") (pintype "passive"))
      (node (ref "JP5") (pin "1") (pinfunction "1_1") (pintype "passive"))
    )
    (net (code "33") (name "Net-(D15--)") (class "Default")
      (node (ref "D15") (pin "2") (pinfunction "-_2") (pintype "passive"))
      (node (ref "Q1") (pin "2") (pinfunction "C_2") (pintype "passive"))
      (node (ref "Q3") (pin "2") (pinfunction "C_2") (pintype "passive"))
      (node (ref "X1") (pin "5") (pinfunction "5_5") (pintype "passive"))
    )
    (net (code "34") (name "Net-(IC3A-A)") (class "Default")
      (node (ref "IC3") (pin "10") (pinfunction "A_10") (pintype "input"))
      (node (ref "R31") (pin "1") (pinfunction "1_1") (pintype "passive"))
      (node (ref "X1") (pin "4") (pinfunction "4_4") (pintype "passive"))
      (node (ref "X3") (pin "2") (pinfunction "S_2") (pintype "passive"))
    )
    (net (code "35") (name "Net-(IC3A-B)") (class "Default")
      (node (ref "IC3") (pin "13") (pinfunction "B_13") (pintype "input"))
      (node (ref "R30") (pin "1") (pinfunction "1_1") (pintype "passive"))
      (node (ref "X1") (pin "3") (pinfunction "3_3") (pintype "passive"))
      (node (ref "X3") (pin "3") (pinfunction "S_3") (pintype "passive"))
    )
    (net (code "36") (name "Net-(IC3A-C)") (class "Default")
      (node (ref "IC3") (pin "12") (pinfunction "C_12") (pintype "input"))
      (node (ref "R29") (pin "1") (pinfunction "1_1") (pintype "passive"))
      (node (ref "X1") (pin "2") (pinfunction "2_2") (pintype "passive"))
      (node (ref "X3") (pin "4") (pinfunction "S_4") (pintype "passive"))
    )
    (net (code "37") (name "Net-(IC3A-Q0)") (class "Default")
      (node (ref "IC3") (pin "3") (pinfunction "Q0_3") (pintype "output"))
      (node (ref "IC6") (pin "1") (pinfunction "I1_1") (pintype "input"))
      (node (ref "IC6") (pin "2") (pinfunction "I2_2") (pintype "input"))
    )
    (net (code "38") (name "Net-(IC3A-Q1)") (class "Default")
      (node (ref "IC3") (pin "14") (pinfunction "Q1_14") (pintype "output"))
      (node (ref "IC6") (pin "6") (pinfunction "I6_6") (pintype "input"))
    )
    (net (code "39") (name "Net-(IC3A-Q2)") (class "Default")
      (node (ref "IC3") (pin "2") (pinfunction "Q2_2") (pintype "output"))
      (node (ref "IC6") (pin "7") (pinfunction "I7_7") (pintype "input"))
    )
    (net (code "40") (name "Net-(IC3A-Q3)") (class "Default")
      (node (ref "IC3") (pin "15") (pinfunction "Q3_15") (pintype "output"))
      (node (ref "IC6") (pin "5") (pinfunction "I5_5") (pintype "input"))
    )
    (net (code "41") (name "Net-(IC3A-Q4)") (class "Default")
      (node (ref "IC3") (pin "1") (pinfunction "Q4_1") (pintype "output"))
      (node (ref "IC6") (pin "4") (pinfunction "I4_4") (pintype "input"))
    )
    (net (code "42") (name "Net-(IC3A-Q5)") (class "Default")
      (node (ref "IC3") (pin "6") (pinfunction "Q5_6") (pintype "output"))
      (node (ref "IC6") (pin "3") (pinfunction "I3_3") (pintype "input"))
    )
    (net (code "43") (name "Net-(IC4-ADJ)") (class "Default")
      (node (ref "IC4") (pin "1") (pinfunction "ADJ_1") (pintype "input"))
      (node (ref "R18") (pin "1") (pinfunction "1_1") (pintype "passive"))
      (node (ref "R5") (pin "2") (pinfunction "2_2") (pintype "passive"))
      (node (ref "X1") (pin "7") (pinfunction "7_7") (pintype "passive"))
    )
    (net (code "44") (name "Net-(IC4-VI)") (class "Default")
      (node (ref "IC4") (pin "3") (pinfunction "VI_3") (pintype "input"))
      (node (ref "Q2") (pin "2") (pinfunction "C_2") (pintype "passive"))
      (node (ref "Q4") (pin "2") (pinfunction "C_2") (pintype "passive"))
    )
    (net (code "45") (name "Net-(IC4-VO)") (class "Default")
      (node (ref "IC4") (pin "2") (pinfunction "VO_2") (pintype "passive"))
      (node (ref "R18") (pin "2") (pinfunction "2_2") (pintype "passive"))
    )
    (net (code "46") (name "Net-(IC5-CV)") (class "Default")
      (node (ref "IC5") (pin "5") (pinfunction "CV_5") (pintype "input"))
      (node (ref "R26") (pin "2") (pinfunction "2_2") (pintype "passive"))
    )
    (net (code "47") (name "Net-(IC5-Q)") (class "Default")
      (node (ref "IC5") (pin "3") (pinfunction "Q_3") (pintype "output"))
      (node (ref "IC8") (pin "12") (pinfunction "A_12") (pintype "input"))
      (node (ref "R26") (pin "1") (pinfunction "1_1") (pintype "passive"))
    )
    (net (code "48") (name "Net-(IC6-O2)") (class "Default")
      (node (ref "IC6") (pin "15") (pinfunction "O2_15") (pintype "open_collector"))
      (node (ref "R13") (pin "1") (pinfunction "1_1") (pintype "passive"))
    )
    (net (code "49") (name "Net-(IC7A-+IN)") (class "Default")
      (node (ref "IC7") (pin "5") (pinfunction "+IN_5") (pintype "input"))
      (node (ref "R15") (pin "1") (pinfunction "1_1") (pintype "passive"))
      (node (ref "R16") (pin "2") (pinfunction "2_2") (pintype "passive"))
      (node (ref "R17") (pin "2") (pinfunction "2_2") (pintype "passive"))
    )
    (net (code "50") (name "Net-(IC7A--IN)") (class "Default")
      (node (ref "C3") (pin "1") (pinfunction "1_1") (pintype "passive"))
      (node (ref "IC7") (pin "4") (pinfunction "-IN_4") (pintype "input"))
      (node (ref "R12") (pin "1") (pinfunction "1_1") (pintype "passive"))
    )
    (net (code "51") (name "Net-(IC7B-+IN)") (class "Default")
      (node (ref "IC7") (pin "7") (pinfunction "+IN_7") (pintype "input"))
      (node (ref "R25") (pin "1") (pinfunction "1_1") (pintype "passive"))
      (node (ref "R6") (pin "1") (pinfunction "1_1") (pintype "passive"))
    )
    (net (code "52") (name "Net-(IC7B--IN)") (class "Default")
      (node (ref "IC7") (pin "6") (pinfunction "-IN_6") (pintype "input"))
      (node (ref "IC7") (pin "8") (pinfunction "-IN_8") (pintype "input"))
      (node (ref "R5") (pin "1") (pinfunction "1_1") (pintype "passive"))
    )
    (net (code "53") (name "Net-(IC7B-OUT)") (class "Default")
      (node (ref "IC7") (pin "1") (pinfunction "OUT_1") (pintype "open_collector"))
      (node (ref "R10") (pin "2") (pinfunction "2_2") (pintype "passive"))
      (node (ref "R19") (pin "2") (pinfunction "2_2") (pintype "passive"))
    )
    (net (code "54") (name "Net-(IC7C-+IN)") (class "Default")
      (node (ref "C5") (pin "1") (pinfunction "1_1") (pintype "passive"))
      (node (ref "IC7") (pin "9") (pinfunction "+IN_9") (pintype "input"))
      (node (ref "R25") (pin "2") (pinfunction "2_2") (pintype "passive"))
      (node (ref "R8") (pin "2") (pinfunction "2_2") (pintype "passive"))
    )
    (net (code "55") (name "Net-(IC7C-OUT)") (class "Default")
      (node (ref "C9") (pin "2") (pinfunction "2_2") (pintype "passive"))
      (node (ref "IC7") (pin "14") (pinfunction "OUT_14") (pintype "open_collector"))
      (node (ref "R9") (pin "2") (pinfunction "2_2") (pintype "passive"))
    )
    (net (code "56") (name "Net-(IC7D-+IN)") (class "Default")
      (node (ref "C8") (pin "1") (pinfunction "1_1") (pintype "passive"))
      (node (ref "IC7") (pin "11") (pinfunction "+IN_11") (pintype "input"))
      (node (ref "R1") (pin "1") (pinfunction "1_1") (pintype "passive"))
    )
    (net (code "57") (name "Net-(IC7D--IN)") (class "Default")
      (node (ref "IC7") (pin "10") (pinfunction "-IN_10") (pintype "input"))
      (node (ref "R2") (pin "2") (pinfunction "2_2") (pintype "passive"))
    )
    (net (code "58") (name "Net-(IC7D-OUT)") (class "Default")
      (node (ref "IC7") (pin "13") (pinfunction "OUT_13") (pintype "open_collector"))
      (node (ref "Q9") (pin "1") (pinfunction "B_1") (pintype "passive"))
      (node (ref "R32") (pin "2") (pinfunction "2_2") (pintype "passive"))
      (node (ref "T3") (pin "B") (pinfunction "B_B") (pintype "passive"))
    )
    (net (code "59") (name "Net-(IC8B-B)") (class "Default")
      (node (ref "IC8") (pin "11") (pinfunction "B_11") (pintype "input"))
      (node (ref "IC8") (pin "9") (pinfunction "~{Q}_9") (pintype "output"))
      (node (ref "R35") (pin "2") (pinfunction "2_2") (pintype "passive"))
    )
    (net (code "60") (name "Net-(IC8B-T2)") (class "Default")
      (node (ref "C10") (pin "1") (pinfunction "1_1") (pintype "passive"))
      (node (ref "IC8") (pin "14") (pinfunction "T2_14") (pintype "input"))
      (node (ref "R34") (pin "1") (pinfunction "1_1") (pintype "passive"))
    )
    (net (code "61") (name "Net-(JP1-Pad2)") (class "Default")
      (node (ref "JP1") (pin "2") (pinfunction "2_2") (pintype "passive"))
      (node (ref "R36") (pin "2") (pinfunction "2_2") (pintype "passive"))
      (node (ref "R37") (pin "2") (pinfunction "2_2") (pintype "passive"))
    )
    (net (code "62") (name "Net-(JP2-Pad1)") (class "Default")
      (node (ref "JP2") (pin "1") (pinfunction "1_1") (pintype "passive"))
      (node (ref "R23") (pin "2") (pinfunction "2_2") (pintype "passive"))
    )
    (net (code "63") (name "Net-(LED1-PadA)") (class "Default")
      (node (ref "LED1") (pin "A") (pinfunction "A_A") (pintype "passive"))
      (node (ref "LED2") (pin "A") (pinfunction "A_A") (pintype "passive"))
      (node (ref "LED3") (pin "A") (pinfunction "A_A") (pintype "passive"))
      (node (ref "LED4") (pin "A") (pinfunction "A_A") (pintype "passive"))
      (node (ref "LED7") (pin "A") (pinfunction "A_A") (pintype "passive"))
      (node (ref "R11") (pin "1") (pinfunction "1_1") (pintype "passive"))
    )
    (net (code "64") (name "Net-(LED6-C)") (class "Default")
      (node (ref "LED6") (pin "K") (pinfunction "C_K") (pintype "passive"))
      (node (ref "R4") (pin "1") (pinfunction "1_1") (pintype "passive"))
    )
    (net (code "65") (name "Net-(Q1-B)") (class "Default")
      (node (ref "Q1") (pin "1") (pinfunction "B_1") (pintype "passive"))
      (node (ref "Q3") (pin "1") (pinfunction "B_1") (pintype "passive"))
      (node (ref "R13") (pin "2") (pinfunction "2_2") (pintype "passive"))
    )
    (net (code "66") (name "Net-(Q2-B)") (class "Default")
      (node (ref "Q2") (pin "1") (pinfunction "B_1") (pintype "passive"))
      (node (ref "Q4") (pin "1") (pinfunction "B_1") (pintype "passive"))
      (node (ref "R9") (pin "1") (pinfunction "1_1") (pintype "passive"))
    )
    (net (code "67") (name "Net-(Q5-B)") (class "Default")
      (node (ref "Q5") (pin "1") (pinfunction "B_1") (pintype "passive"))
      (node (ref "Q6") (pin "1") (pinfunction "B_1") (pintype "passive"))
      (node (ref "Q6") (pin "2") (pinfunction "C_2") (pintype "passive"))
      (node (ref "Q7") (pin "1") (pinfunction "B_1") (pintype "passive"))
      (node (ref "Q7") (pin "2") (pinfunction "C_2") (pintype "passive"))
      (node (ref "Q8") (pin "1") (pinfunction "B_1") (pintype "passive"))
      (node (ref "R38") (pin "1") (pinfunction "1_1") (pintype "passive"))
      (node (ref "R39") (pin "1") (pinfunction "1_1") (pintype "passive"))
      (node (ref "T1") (pin "2") (pinfunction "B_2") (pintype "passive"))
      (node (ref "T1") (pin "4") (pinfunction "B_4") (pintype "passive"))
      (node (ref "T1") (pin "6") (pinfunction "C1_6") (pintype "passive"))
      (node (ref "X2") (pin "2") (pinfunction "S_2") (pintype "passive"))
    )
    (net (code "68") (name "Net-(Q5-E)") (class "Default")
      (node (ref "Q5") (pin "3") (pinfunction "E_3") (pintype "passive"))
      (node (ref "Q8") (pin "3") (pinfunction "E_3") (pintype "passive"))
      (node (ref "R21") (pin "2") (pinfunction "2_2") (pintype "passive"))
      (node (ref "T1") (pin "1") (pinfunction "E_1") (pintype "passive"))
    )
    (net (code "69") (name "Net-(Q6-E)") (class "Default")
      (node (ref "Q6") (pin "3") (pinfunction "E_3") (pintype "passive"))
      (node (ref "Q7") (pin "3") (pinfunction "E_3") (pintype "passive"))
      (node (ref "R20") (pin "2") (pinfunction "2_2") (pintype "passive"))
      (node (ref "T1") (pin "3") (pinfunction "E_3") (pintype "passive"))
    )
    (net (code "70") (name "Net-(Q9-C)") (class "Default")
      (node (ref "Q9") (pin "2") (pinfunction "C_2") (pintype "passive"))
      (node (ref "R3") (pin "2") (pinfunction "2_2") (pintype "passive"))
      (node (ref "T3") (pin "C") (pinfunction "C_C") (pintype "passive"))
      (node (ref "X1") (pin "21") (pinfunction "21_21") (pintype "passive"))
    )
    (net (code "71") (name "Net-(Q10-D)") (class "Default")
      (node (ref "Q10") (pin "3") (pinfunction "D_3") (pintype "passive"))
      (node (ref "R7") (pin "2") (pinfunction "2_2") (pintype "passive"))
    )
    (net (code "72") (name "Net-(R1-Pad2)") (class "Default")
      (node (ref "R1") (pin "2") (pinfunction "2_2") (pintype "passive"))
      (node (ref "X1") (pin "22") (pinfunction "22_22") (pintype "passive"))
    )
    (net (code "73") (name "Net-(R27-Pad2)") (class "Default")
      (node (ref "R27") (pin "2") (pinfunction "2_2") (pintype "passive"))
      (node (ref "R28") (pin "1") (pinfunction "1_1") (pintype "passive"))
    )
    (net (code "74") (name "Net-(R33-Pad2)") (class "Default")
      (node (ref "R33") (pin "2") (pinfunction "2_2") (pintype "passive"))
      (node (ref "X1") (pin "16") (pinfunction "16_16") (pintype "passive"))
    )
    (net (code "75") (name "Net-(TACHO_BEL-PP)") (class "Default")
      (node (ref "TACHO_BEL") (pin "TP") (pinfunction "PP_TP") (pintype "input"))
      (node (ref "X1") (pin "24") (pinfunction "24_24") (pintype "passive"))
    )
    (net (code "76") (name "VCC") (class "Default")
      (node (ref "C4") (pin "1") (pinfunction "1_1") (pintype "passive"))
      (node (ref "IC1") (pin "OUT") (pinfunction "OUT_OUT") (pintype "passive"))
      (node (ref "IC2") (pin "1") (pinfunction "OUT_1") (pintype "passive"))
      (node (ref "IC7") (pin "3") (pinfunction "V+_3") (pintype "power_in"))
      (node (ref "R11") (pin "2") (pinfunction "2_2") (pintype "passive"))
      (node (ref "R15") (pin "2") (pinfunction "2_2") (pintype "passive"))
      (node (ref "R19") (pin "1") (pinfunction "1_1") (pintype "passive"))
      (node (ref "R6") (pin "2") (pinfunction "2_2") (pintype "passive"))
    )
    (net (code "77") (name "unconnected-(IC3A-Q6-Pad7)") (class "Default")
      (node (ref "IC3") (pin "7") (pinfunction "Q6_7") (pintype "output"))
    )
    (net (code "78") (name "unconnected-(IC3A-Q7-Pad4)") (class "Default")
      (node (ref "IC3") (pin "4") (pinfunction "Q7_4") (pintype "output"))
    )
    (net (code "79") (name "unconnected-(IC3A-Q8-Pad9)") (class "Default")
      (node (ref "IC3") (pin "9") (pinfunction "Q8_9") (pintype "output"))
    )
    (net (code "80") (name "unconnected-(IC3A-Q9-Pad5)") (class "Default")
      (node (ref "IC3") (pin "5") (pinfunction "Q9_5") (pintype "output"))
    )
    (net (code "81") (name "unconnected-(IC5-DIS-Pad7)") (class "Default")
      (node (ref "IC5") (pin "7") (pinfunction "DIS_7") (pintype "input"))
    )
    (net (code "82") (name "unconnected-(IC6-CD+-Pad9)") (class "Default")
      (node (ref "IC6") (pin "9") (pinfunction "CD+_9") (pintype "passive"))
    )
    (net (code "83") (name "unconnected-(IC8A-Q-Pad6)") (class "Default")
      (node (ref "IC8") (pin "6") (pinfunction "Q_6") (pintype "output"))
    )
    (net (code "84") (name "unconnected-(IC8A-T2-Pad2)") (class "Default")
      (node (ref "IC8") (pin "2") (pinfunction "T2_2") (pintype "input"))
    )
    (net (code "85") (name "unconnected-(IC8A-~{Q}-Pad7)") (class "Default")
      (node (ref "IC8") (pin "7") (pinfunction "~{Q}_7") (pintype "output"))
    )
    (net (code "86") (name "unconnected-(IC8B-Q-Pad10)") (class "Default")
      (node (ref "IC8") (pin "10") (pinfunction "Q_10") (pintype "output"))
    )
    (net (code "87") (name "unconnected-(JP2-Pad3)") (class "Default")
      (node (ref "JP2") (pin "3") (pinfunction "3_3") (pintype "passive"))
    )
    (net (code "88") (name "unconnected-(Q3-C{slash}-Pad4)") (class "Default")
      (node (ref "Q3") (pin "4") (pinfunction "C/_4") (pintype "passive"))
    )
    (net (code "89") (name "unconnected-(Q4-C{slash}-Pad4)") (class "Default")
      (node (ref "Q4") (pin "4") (pinfunction "C/_4") (pintype "passive"))
    )
    (net (code "90") (name "unconnected-(Q5-C{slash}-Pad4)") (class "Default")
      (node (ref "Q5") (pin "4") (pinfunction "C/_4") (pintype "passive"))
    )
    (net (code "91") (name "unconnected-(Q6-C{slash}-Pad4)") (class "Default")
      (node (ref "Q6") (pin "4") (pinfunction "C/_4") (pintype "passive"))
    )
    (net (code "92") (name "unconnected-(T1A-C-Pad5)") (class "Default")
      (node (ref "T1") (pin "5") (pinfunction "C_5") (pintype "passive"))
    )
    (net (code "93") (name "unconnected-(T1B-C-Pad7)") (class "Default")
      (node (ref "T1") (pin "7") (pinfunction "C_7") (pintype "passive"))
    )
    (net (code "94") (name "unconnected-(X1-Pad20)") (class "Default")
      (node (ref "X1") (pin "20") (pinfunction "20_20") (pintype "passive"))
    )
  )
)
